# 12v_to_3v3_dbl.net
KiCad netlist of a schematic drawn in EAGLE
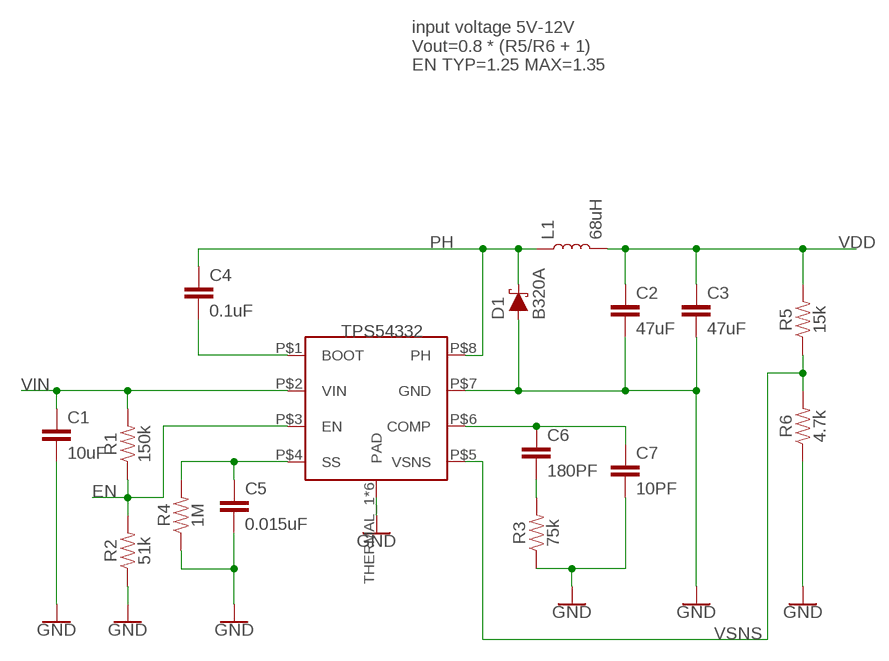
[diagram p0: schematic, sheet 1]

(export (version "E")
  (design (tool "Eeschema 10.0.6"))
  (components
    (comp (ref "C1")
      (value "10uF")
      (footprint "eagle-import:0805")
      (libsource (lib "eagle-import") (part "10UF-0805-10V-10%"))
    )
    (comp (ref "C2")
      (value "47uF")
      (footprint "eagle-import:0805")
      (libsource (lib "eagle-import") (part "22UF-0805-6.3V-20%"))
    )
    (comp (ref "C3")
      (value "47uF")
      (footprint "eagle-import:0805")
      (libsource (lib "eagle-import") (part "22UF-0805-6.3V-20%"))
    )
    (comp (ref "C4")
      (value "0.1uF")
      (footprint "eagle-import:0402")
      (libsource (lib "eagle-import") (part "0.1UF-0402-16V-10%"))
    )
    (comp (ref "C5")
      (value "0.015uF")
      (footprint "eagle-import:0402")
      (libsource (lib "eagle-import") (part "0.1UF-0402-16V-10%"))
    )
    (comp (ref "C6")
      (value "180PF")
      (footprint "eagle-import:0402")
      (libsource (lib "eagle-import") (part "100PF-0402-50V-5%"))
    )
    (comp (ref "C7")
      (value "10PF")
      (footprint "eagle-import:0402")
      (libsource (lib "eagle-import") (part "100PF-0402-50V-5%"))
    )
    (comp (ref "D1")
      (value "B320A")
      (footprint "eagle-import:SMA")
      (libsource (lib "eagle-import") (part "B320A"))
    )
    (comp (ref "L1")
      (value "68uH")
      (footprint "eagle-import:1210")
      (libsource (lib "eagle-import") (part "100UH_SMD"))
    )
    (comp (ref "R1")
      (value "150k")
      (footprint "eagle-import:0402")
      (libsource (lib "eagle-import") (part "RESISTOR0402"))
    )
    (comp (ref "R2")
      (value "51k")
      (footprint "eagle-import:0402")
      (libsource (lib "eagle-import") (part "RESISTOR0402"))
    )
    (comp (ref "R3")
      (value "75k")
      (footprint "eagle-import:0402")
      (libsource (lib "eagle-import") (part "RESISTOR0402"))
    )
    (comp (ref "R4")
      (value "1M")
      (footprint "eagle-import:0402")
      (libsource (lib "eagle-import") (part "RESISTOR0402"))
    )
    (comp (ref "R5")
      (value "15k")
      (footprint "eagle-import:0402")
      (libsource (lib "eagle-import") (part "RESISTOR0402"))
    )
    (comp (ref "R6")
      (value "4.7k")
      (footprint "eagle-import:0402")
      (libsource (lib "eagle-import") (part "RESISTOR0402"))
    )
    (comp (ref "U1")
      (value "TPS54332A")
      (footprint "eagle-import:DDA(8-POWERSOIC)_THERAL")
      (libsource (lib "eagle-import") (part "TPS54332A"))
    )
  )
  (nets
    (net (code "1") (name "/EN") (class "Default")
      (node (ref "R1") (pin "1") (pinfunction "1_1") (pintype "passive"))
      (node (ref "R2") (pin "2") (pinfunction "2_2") (pintype "passive"))
      (node (ref "U1") (pin "P$3") (pinfunction "EN_P$3") (pintype "bidirectional"))
    )
    (net (code "2") (name "/PH") (class "Default")
      (node (ref "C4") (pin "1") (pinfunction "1_1") (pintype "passive"))
      (node (ref "D1") (pin "C") (pinfunction "C_C") (pintype "passive"))
      (node (ref "L1") (pin "P$1") (pinfunction "1_P$1") (pintype "passive"))
      (node (ref "U1") (pin "P$8") (pinfunction "PH_P$8") (pintype "bidirectional"))
    )
    (net (code "3") (name "/VDD") (class "Default")
      (node (ref "C2") (pin "1") (pinfunction "1_1") (pintype "passive"))
      (node (ref "C3") (pin "1") (pinfunction "1_1") (pintype "passive"))
      (node (ref "L1") (pin "P$2") (pinfunction "2_P$2") (pintype "passive"))
      (node (ref "R5") (pin "2") (pinfunction "2_2") (pintype "passive"))
    )
    (net (code "4") (name "/VIN") (class "Default")
      (node (ref "C1") (pin "1") (pinfunction "1_1") (pintype "passive"))
      (node (ref "R1") (pin "2") (pinfunction "2_2") (pintype "passive"))
      (node (ref "U1") (pin "P$2") (pinfunction "VIN_P$2") (pintype "bidirectional"))
    )
    (net (code "5") (name "/VSNS") (class "Default")
      (node (ref "R5") (pin "1") (pinfunction "1_1") (pintype "passive"))
      (node (ref "R6") (pin "2") (pinfunction "2_2") (pintype "passive"))
      (node (ref "U1") (pin "P$5") (pinfunction "VSNS_P$5") (pintype "bidirectional"))
    )
    (net (code "6") (name "GND") (class "Default")
      (node (ref "C1") (pin "2") (pinfunction "2_2") (pintype "passive"))
      (node (ref "C2") (pin "2") (pinfunction "2_2") (pintype "passive"))
      (node (ref "C3") (pin "2") (pinfunction "2_2") (pintype "passive"))
      (node (ref "C5") (pin "2") (pinfunction "2_2") (pintype "passive"))
      (node (ref "C7") (pin "2") (pinfunction "2_2") (pintype "passive"))
      (node (ref "D1") (pin "A") (pinfunction "A_A") (pintype "passive"))
      (node (ref "R2") (pin "1") (pinfunction "1_1") (pintype "passive"))
      (node (ref "R3") (pin "1") (pinfunction "1_1") (pintype "passive"))
      (node (ref "R4") (pin "1") (pinfunction "1_1") (pintype "passive"))
      (node (ref "R6") (pin "1") (pinfunction "1_1") (pintype "passive"))
      (node (ref "U1") (pin "P$7") (pinfunction "GND_P$7") (pintype "bidirectional"))
      (node (ref "U1") (pin "THERMAL_1") (pinfunction "PAD_THERMAL_1") (pintype "bidirectional"))
      (node (ref "U1") (pin "THERMAL_2") (pinfunction "PAD_THERMAL_2") (pintype "bidirectional"))
      (node (ref "U1") (pin "THERMAL_3") (pinfunction "PAD_THERMAL_3") (pintype "bidirectional"))
      (node (ref "U1") (pin "THERMAL_4") (pinfunction "PAD_THERMAL_4") (pintype "bidirectional"))
      (node (ref "U1") (pin "THERMAL_5") (pinfunction "PAD_THERMAL_5") (pintype "bidirectional"))
      (node (ref "U1") (pin "THERMAL_6") (pinfunction "PAD_THERMAL_6") (pintype "bidirectional"))
    )
    (net (code "7") (name "Net-(C6-Pad2)") (class "Default")
      (node (ref "C6") (pin "2") (pinfunction "2_2") (pintype "passive"))
      (node (ref "R3") (pin "2") (pinfunction "2_2") (pintype "passive"))
    )
    (net (code "8") (name "Net-(U1-BOOT)") (class "Default")
      (node (ref "C4") (pin "2") (pinfunction "2_2") (pintype "passive"))
      (node (ref "U1") (pin "P$1") (pinfunction "BOOT_P$1") (pintype "bidirectional"))
    )
    (net (code "9") (name "Net-(U1-COMP)") (class "Default")
      (node (ref "C6") (pin "1") (pinfunction "1_1") (pintype "passive"))
      (node (ref "C7") (pin "1") (pinfunction "1_1") (pintype "passive"))
      (node (ref "U1") (pin "P$6") (pinfunction "COMP_P$6") (pintype "bidirectional"))
    )
    (net (code "10") (name "Net-(U1-SS)") (class "Default")
      (node (ref "C5") (pin "1") (pinfunction "1_1") (pintype "passive"))
      (node (ref "R4") (pin "2") (pinfunction "2_2") (pintype "passive"))
      (node (ref "U1") (pin "P$4") (pinfunction "SS_P$4") (pintype "bidirectional"))
    )
  )
)
